# LB_BIT_w21_SUM-v03_2_1x.net
KiCad netlist of a schematic drawn in EAGLE
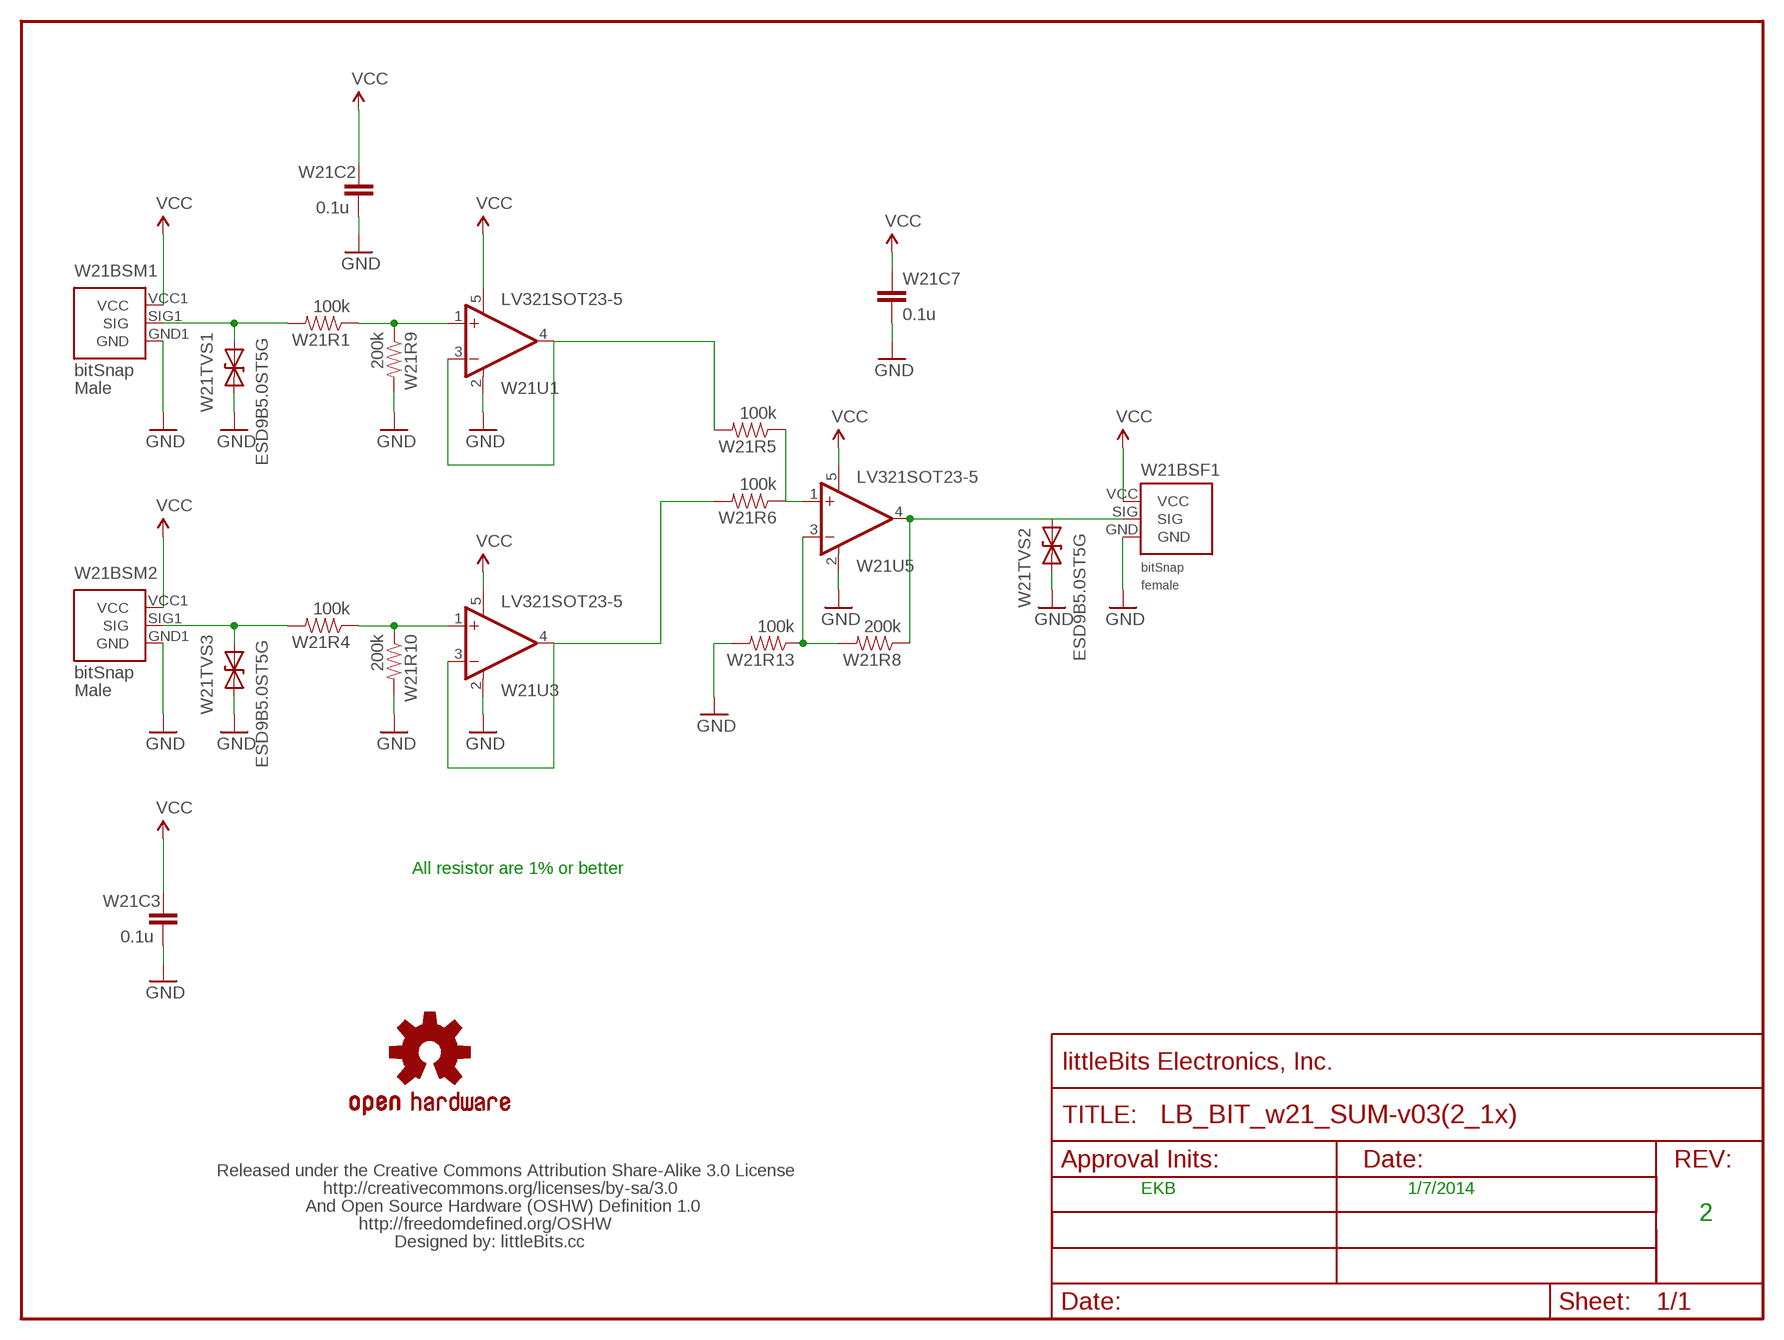
[diagram p0: schematic, sheet 1]

(export (version "E")
  (design (tool "Eeschema 10.0.6"))
  (components
    (comp (ref "FRAME1")
      (value "FRAME-LETTER")
      (footprint "eagle-import:FABDWG01")
      (libsource (lib "eagle-import") (part "FRAME-LETTER"))
    )
    (comp (ref "U$1")
      (value "OSHW-LOGOS")
      (footprint "eagle-import:OSHW-LOGO-S")
      (libsource (lib "eagle-import") (part "OSHW-LOGOS"))
    )
    (comp (ref "U$2")
      (value "OSHWCREDIT")
      (footprint "eagle-import:OSHWCREDIT")
      (libsource (lib "eagle-import") (part "OSHWCREDIT"))
    )
    (comp (ref "W21BSF1")
      (value "BITSNAP_V03_FEMALE")
      (footprint "eagle-import:BITSNAP_V03_FEMALE")
      (libsource (lib "eagle-import") (part "BITSNAP_V03_FEMALE"))
    )
    (comp (ref "W21BSM1")
      (value "BITSNAP_V03_MALE")
      (footprint "eagle-import:BITSNAP_V03_MALE")
      (libsource (lib "eagle-import") (part "BITSNAP_V03_MALE"))
    )
    (comp (ref "W21BSM2")
      (value "BITSNAP_V03_MALE")
      (footprint "eagle-import:BITSNAP_V03_MALE")
      (libsource (lib "eagle-import") (part "BITSNAP_V03_MALE"))
    )
    (comp (ref "W21C2")
      (value "0.1u")
      (footprint "eagle-import:CAP-0603")
      (libsource (lib "eagle-import") (part "CAPCAP-0603"))
    )
    (comp (ref "W21C3")
      (value "0.1u")
      (footprint "eagle-import:CAP-0603")
      (libsource (lib "eagle-import") (part "CAPCAP-0603"))
    )
    (comp (ref "W21C7")
      (value "0.1u")
      (footprint "eagle-import:CAP-0603")
      (libsource (lib "eagle-import") (part "CAPCAP-0603"))
    )
    (comp (ref "W21R1")
      (value "100k")
      (footprint "eagle-import:RES-0603")
      (libsource (lib "eagle-import") (part "RESISTOR0603"))
    )
    (comp (ref "W21R4")
      (value "100k")
      (footprint "eagle-import:RES-0603")
      (libsource (lib "eagle-import") (part "RESISTOR0603"))
    )
    (comp (ref "W21R5")
      (value "100k")
      (footprint "eagle-import:RES-0603")
      (libsource (lib "eagle-import") (part "RESISTOR0603"))
    )
    (comp (ref "W21R6")
      (value "100k")
      (footprint "eagle-import:RES-0603")
      (libsource (lib "eagle-import") (part "RESISTOR0603"))
    )
    (comp (ref "W21R8")
      (value "200k")
      (footprint "eagle-import:RES-0603")
      (libsource (lib "eagle-import") (part "RESISTOR0603"))
    )
    (comp (ref "W21R9")
      (value "200k")
      (footprint "eagle-import:RES-0603")
      (libsource (lib "eagle-import") (part "RESISTOR0603"))
    )
    (comp (ref "W21R10")
      (value "200k")
      (footprint "eagle-import:RES-0603")
      (libsource (lib "eagle-import") (part "RESISTOR0603"))
    )
    (comp (ref "W21R13")
      (value "100k")
      (footprint "eagle-import:RES-0603")
      (libsource (lib "eagle-import") (part "RESISTOR0603"))
    )
    (comp (ref "W21TVS1")
      (value "ESD9B5.0ST5G")
      (footprint "eagle-import:SOD-923")
      (libsource (lib "eagle-import") (part "DIODE-TVSSOD-923"))
    )
    (comp (ref "W21TVS2")
      (value "ESD9B5.0ST5G")
      (footprint "eagle-import:SOD-923")
      (libsource (lib "eagle-import") (part "DIODE-TVSSOD-923"))
    )
    (comp (ref "W21TVS3")
      (value "ESD9B5.0ST5G")
      (footprint "eagle-import:SOD-923")
      (libsource (lib "eagle-import") (part "DIODE-TVSSOD-923"))
    )
    (comp (ref "W21U1")
      (value "LV321SOT23-5")
      (footprint "eagle-import:SOT23-5")
      (libsource (lib "eagle-import") (part "LV321SOT23-5"))
    )
    (comp (ref "W21U3")
      (value "LV321SOT23-5")
      (footprint "eagle-import:SOT23-5")
      (libsource (lib "eagle-import") (part "LV321SOT23-5"))
    )
    (comp (ref "W21U5")
      (value "LV321SOT23-5")
      (footprint "eagle-import:SOT23-5")
      (libsource (lib "eagle-import") (part "LV321SOT23-5"))
    )
  )
  (nets
    (net (code "1") (name "GND") (class "Default")
      (node (ref "W21BSF1") (pin "GND") (pinfunction "GND_GND") (pintype "bidirectional"))
      (node (ref "W21BSM1") (pin "GND1") (pinfunction "GND_GND1") (pintype "bidirectional"))
      (node (ref "W21BSM2") (pin "GND1") (pinfunction "GND_GND1") (pintype "bidirectional"))
      (node (ref "W21C2") (pin "2") (pinfunction "2_2") (pintype "passive"))
      (node (ref "W21C3") (pin "2") (pinfunction "2_2") (pintype "passive"))
      (node (ref "W21C7") (pin "2") (pinfunction "2_2") (pintype "passive"))
      (node (ref "W21R10") (pin "2") (pinfunction "2_2") (pintype "passive"))
      (node (ref "W21R13") (pin "2") (pinfunction "2_2") (pintype "passive"))
      (node (ref "W21R9") (pin "2") (pinfunction "2_2") (pintype "passive"))
      (node (ref "W21TVS1") (pin "1") (pinfunction "A_1") (pintype "passive"))
      (node (ref "W21TVS2") (pin "1") (pinfunction "A_1") (pintype "passive"))
      (node (ref "W21TVS3") (pin "1") (pinfunction "A_1") (pintype "passive"))
      (node (ref "W21U1") (pin "2") (pinfunction "V-_2") (pintype "power_in"))
      (node (ref "W21U3") (pin "2") (pinfunction "V-_2") (pintype "power_in"))
      (node (ref "W21U5") (pin "2") (pinfunction "V-_2") (pintype "power_in"))
    )
    (net (code "2") (name "Net-(W21BSM1-SIG)") (class "Default")
      (node (ref "W21BSM1") (pin "SIG1") (pinfunction "SIG_SIG1") (pintype "bidirectional"))
      (node (ref "W21R1") (pin "2") (pinfunction "2_2") (pintype "passive"))
      (node (ref "W21TVS1") (pin "2") (pinfunction "C_2") (pintype "passive"))
    )
    (net (code "3") (name "Net-(W21BSM2-SIG)") (class "Default")
      (node (ref "W21BSM2") (pin "SIG1") (pinfunction "SIG_SIG1") (pintype "bidirectional"))
      (node (ref "W21R4") (pin "2") (pinfunction "2_2") (pintype "passive"))
      (node (ref "W21TVS3") (pin "2") (pinfunction "C_2") (pintype "passive"))
    )
    (net (code "4") (name "Net-(W21TVS2-C)") (class "Default")
      (node (ref "W21BSF1") (pin "SIG") (pinfunction "SIG_SIG") (pintype "bidirectional"))
      (node (ref "W21R8") (pin "1") (pinfunction "1_1") (pintype "passive"))
      (node (ref "W21TVS2") (pin "2") (pinfunction "C_2") (pintype "passive"))
      (node (ref "W21U5") (pin "4") (pinfunction "OUT_4") (pintype "output"))
    )
    (net (code "5") (name "Net-(W21U1-+IN)") (class "Default")
      (node (ref "W21R1") (pin "1") (pinfunction "1_1") (pintype "passive"))
      (node (ref "W21R9") (pin "1") (pinfunction "1_1") (pintype "passive"))
      (node (ref "W21U1") (pin "1") (pinfunction "+IN_1") (pintype "input"))
    )
    (net (code "6") (name "Net-(W21U1--IN)") (class "Default")
      (node (ref "W21R5") (pin "2") (pinfunction "2_2") (pintype "passive"))
      (node (ref "W21U1") (pin "3") (pinfunction "-IN_3") (pintype "input"))
      (node (ref "W21U1") (pin "4") (pinfunction "OUT_4") (pintype "output"))
    )
    (net (code "7") (name "Net-(W21U3-+IN)") (class "Default")
      (node (ref "W21R10") (pin "1") (pinfunction "1_1") (pintype "passive"))
      (node (ref "W21R4") (pin "1") (pinfunction "1_1") (pintype "passive"))
      (node (ref "W21U3") (pin "1") (pinfunction "+IN_1") (pintype "input"))
    )
    (net (code "8") (name "Net-(W21U3--IN)") (class "Default")
      (node (ref "W21R6") (pin "2") (pinfunction "2_2") (pintype "passive"))
      (node (ref "W21U3") (pin "3") (pinfunction "-IN_3") (pintype "input"))
      (node (ref "W21U3") (pin "4") (pinfunction "OUT_4") (pintype "output"))
    )
    (net (code "9") (name "Net-(W21U5-+IN)") (class "Default")
      (node (ref "W21R5") (pin "1") (pinfunction "1_1") (pintype "passive"))
      (node (ref "W21R6") (pin "1") (pinfunction "1_1") (pintype "passive"))
      (node (ref "W21U5") (pin "1") (pinfunction "+IN_1") (pintype "input"))
    )
    (net (code "10") (name "Net-(W21U5--IN)") (class "Default")
      (node (ref "W21R13") (pin "1") (pinfunction "1_1") (pintype "passive"))
      (node (ref "W21R8") (pin "2") (pinfunction "2_2") (pintype "passive"))
      (node (ref "W21U5") (pin "3") (pinfunction "-IN_3") (pintype "input"))
    )
    (net (code "11") (name "VCC") (class "Default")
      (node (ref "W21BSF1") (pin "VCC") (pinfunction "VCC_VCC") (pintype "bidirectional"))
      (node (ref "W21BSM1") (pin "VCC1") (pinfunction "VCC_VCC1") (pintype "bidirectional"))
      (node (ref "W21BSM2") (pin "VCC1") (pinfunction "VCC_VCC1") (pintype "bidirectional"))
      (node (ref "W21C2") (pin "1") (pinfunction "1_1") (pintype "passive"))
      (node (ref "W21C3") (pin "1") (pinfunction "1_1") (pintype "passive"))
      (node (ref "W21C7") (pin "1") (pinfunction "1_1") (pintype "passive"))
      (node (ref "W21U1") (pin "5") (pinfunction "V+_5") (pintype "power_in"))
      (node (ref "W21U3") (pin "5") (pinfunction "V+_5") (pintype "power_in"))
      (node (ref "W21U5") (pin "5") (pinfunction "V+_5") (pintype "power_in"))
    )
  )
)
